# engine_driver.net
KiCad netlist of a schematic drawn in EAGLE
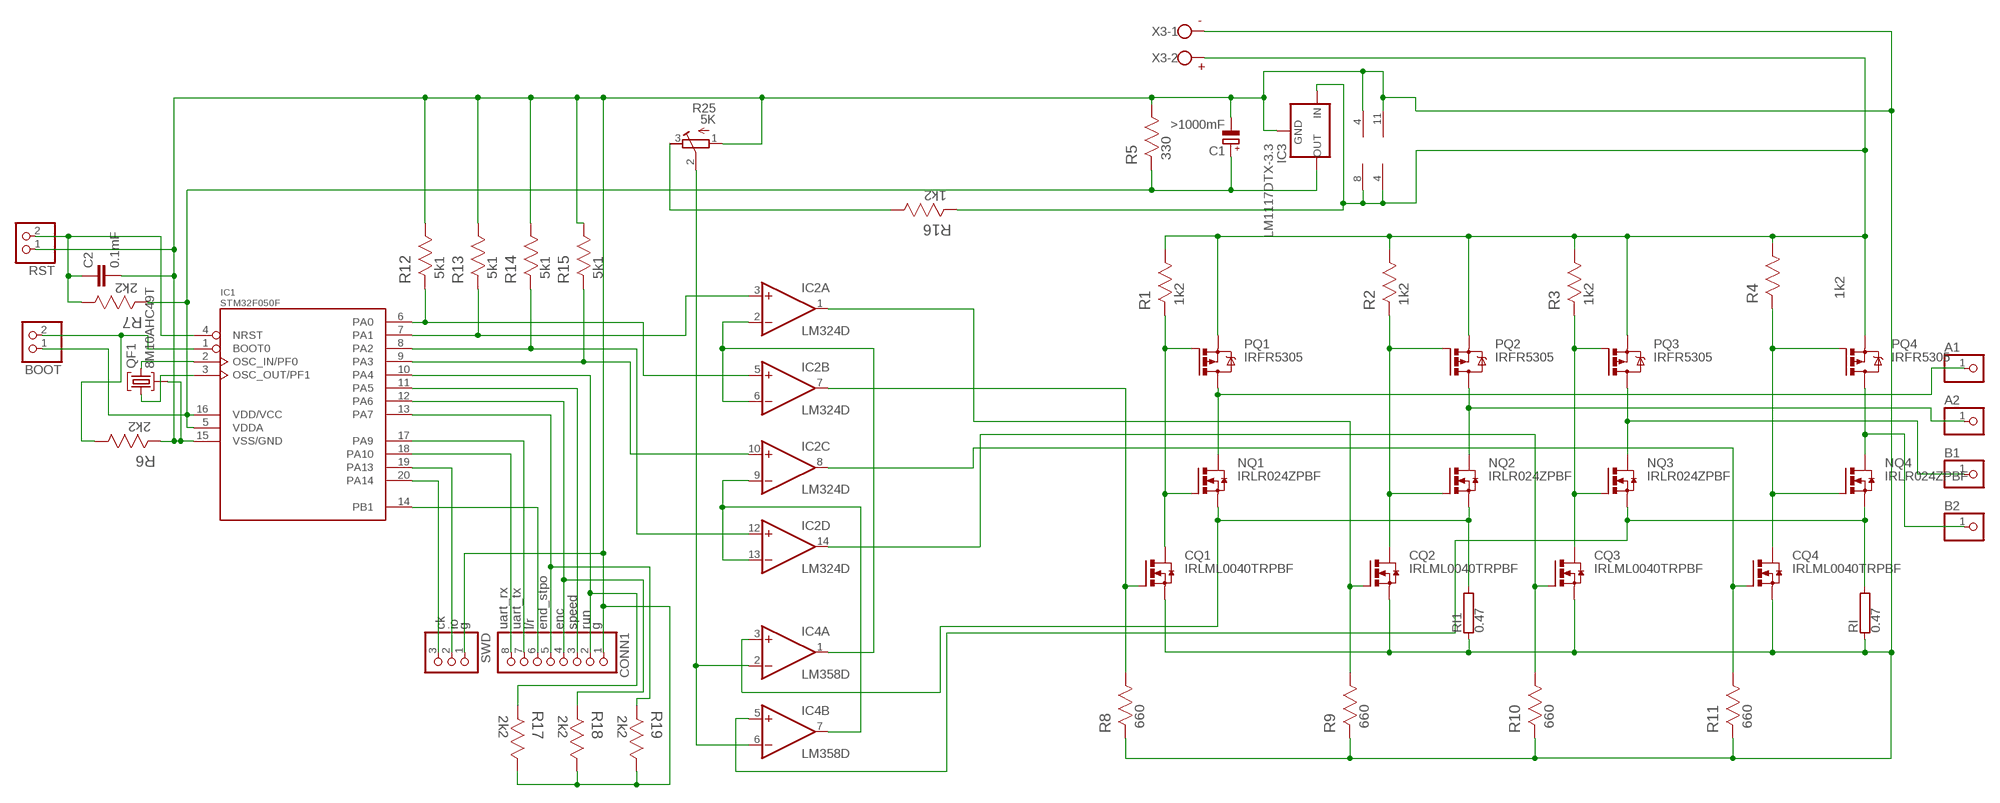
[diagram p0: schematic, sheet 1]

(export (version "E")
  (design (tool "Eeschema 10.0.6"))
  (components
    (comp (ref "A1")
      (value "PINHD-1X1")
      (footprint "eagle-import:1X01")
      (libsource (lib "eagle-import") (part "PINHD-1X1"))
    )
    (comp (ref "A2")
      (value "PINHD-1X1")
      (footprint "eagle-import:1X01")
      (libsource (lib "eagle-import") (part "PINHD-1X1"))
    )
    (comp (ref "B1")
      (value "PINHD-1X1")
      (footprint "eagle-import:1X01")
      (libsource (lib "eagle-import") (part "PINHD-1X1"))
    )
    (comp (ref "B2")
      (value "PINHD-1X1")
      (footprint "eagle-import:1X01")
      (libsource (lib "eagle-import") (part "PINHD-1X1"))
    )
    (comp (ref "BOOT")
      (value "PINHD-1X2")
      (footprint "eagle-import:1X02")
      (libsource (lib "eagle-import") (part "PINHD-1X2"))
    )
    (comp (ref "C1")
      (value ">1000mF")
      (footprint "eagle-import:E2-5")
      (libsource (lib "eagle-import") (part "CPOL-EUE2-5"))
    )
    (comp (ref "C2")
      (value "0.1mF")
      (footprint "eagle-import:C1206")
      (libsource (lib "eagle-import") (part "C-EUC1206"))
    )
    (comp (ref "CONN1")
      (value "PINHD-1X8")
      (footprint "eagle-import:1X08")
      (libsource (lib "eagle-import") (part "PINHD-1X8"))
    )
    (comp (ref "CQ1")
      (value "IRLML0040TRPBF")
      (footprint "eagle-import:MICRO3")
      (libsource (lib "eagle-import") (part "IRLML0040TRPBF"))
    )
    (comp (ref "CQ2")
      (value "IRLML0040TRPBF")
      (footprint "eagle-import:MICRO3")
      (libsource (lib "eagle-import") (part "IRLML0040TRPBF"))
    )
    (comp (ref "CQ3")
      (value "IRLML0040TRPBF")
      (footprint "eagle-import:MICRO3")
      (libsource (lib "eagle-import") (part "IRLML0040TRPBF"))
    )
    (comp (ref "CQ4")
      (value "IRLML0040TRPBF")
      (footprint "eagle-import:MICRO3")
      (libsource (lib "eagle-import") (part "IRLML0040TRPBF"))
    )
    (comp (ref "IC1")
      (value "STM32F050F")
      (footprint "eagle-import:TSSOP20")
      (libsource (lib "eagle-import") (part "STM32F050F"))
    )
    (comp (ref "IC2")
      (value "LM324D")
      (footprint "eagle-import:SO14")
      (libsource (lib "eagle-import") (part "LM324D"))
    )
    (comp (ref "IC3")
      (value "LM1117DTX-3.3")
      (footprint "eagle-import:TO252")
      (libsource (lib "eagle-import") (part "LM1117DTX-3.3"))
    )
    (comp (ref "IC4")
      (value "LM358D")
      (footprint "eagle-import:SO08")
      (libsource (lib "eagle-import") (part "LM358D"))
    )
    (comp (ref "NQ1")
      (value "IRLR024ZPBF")
      (footprint "eagle-import:D-PAK_TO252AA")
      (libsource (lib "eagle-import") (part "IRLR024ZPBF"))
    )
    (comp (ref "NQ2")
      (value "IRLR024ZPBF")
      (footprint "eagle-import:D-PAK_TO252AA")
      (libsource (lib "eagle-import") (part "IRLR024ZPBF"))
    )
    (comp (ref "NQ3")
      (value "IRLR024ZPBF")
      (footprint "eagle-import:D-PAK_TO252AA")
      (libsource (lib "eagle-import") (part "IRLR024ZPBF"))
    )
    (comp (ref "NQ4")
      (value "IRLR024ZPBF")
      (footprint "eagle-import:D-PAK_TO252AA")
      (libsource (lib "eagle-import") (part "IRLR024ZPBF"))
    )
    (comp (ref "PQ1")
      (value "IRFR5305")
      (footprint "eagle-import:D-PAK_TO252AA")
      (libsource (lib "eagle-import") (part "IRF?5305R"))
    )
    (comp (ref "PQ2")
      (value "IRFR5305")
      (footprint "eagle-import:D-PAK_TO252AA")
      (libsource (lib "eagle-import") (part "IRF?5305R"))
    )
    (comp (ref "PQ3")
      (value "IRFR5305")
      (footprint "eagle-import:D-PAK_TO252AA")
      (libsource (lib "eagle-import") (part "IRF?5305R"))
    )
    (comp (ref "PQ4")
      (value "IRFR5305")
      (footprint "eagle-import:D-PAK_TO252AA")
      (libsource (lib "eagle-import") (part "IRF?5305R"))
    )
    (comp (ref "QF1")
      (value "8M10AHC49T")
      (footprint "eagle-import:HC49U")
      (libsource (lib "eagle-import") (part "8M10AHC49T"))
    )
    (comp (ref "R1")
      (value "1k2")
      (footprint "eagle-import:RESC3216X71N")
      (fields (field (name "MPN") "TNPW1206100KBEEA") (field (name "TOLERANCE") "±0.1%"))
      (libsource (lib "eagle-import") (part "TNPW1206100KBEEA"))
    )
    (comp (ref "R2")
      (value "1k2")
      (footprint "eagle-import:RESC3216X71N")
      (fields (field (name "MPN") "TNPW1206100KBEEA") (field (name "TOLERANCE") "±0.1%"))
      (libsource (lib "eagle-import") (part "TNPW1206100KBEEA"))
    )
    (comp (ref "R3")
      (value "1k2")
      (footprint "eagle-import:RESC3216X71N")
      (fields (field (name "MPN") "TNPW1206100KBEEA") (field (name "TOLERANCE") "±0.1%"))
      (libsource (lib "eagle-import") (part "TNPW1206100KBEEA"))
    )
    (comp (ref "R4")
      (value "1k2")
      (footprint "eagle-import:RESC3216X71N")
      (fields (field (name "MPN") "TNPW1206100KBEEA") (field (name "TOLERANCE") "±0.1%"))
      (libsource (lib "eagle-import") (part "TNPW1206100KBEEA"))
    )
    (comp (ref "R5")
      (value "330")
      (footprint "eagle-import:RESC3216X71N")
      (fields (field (name "MPN") "TNPW1206100KBEEA") (field (name "TOLERANCE") "±0.1%"))
      (libsource (lib "eagle-import") (part "TNPW1206100KBEEA"))
    )
    (comp (ref "R6")
      (value "2k2")
      (footprint "eagle-import:RESC3216X71N")
      (fields (field (name "MPN") "TNPW1206100KBEEA") (field (name "TOLERANCE") "±0.1%"))
      (libsource (lib "eagle-import") (part "TNPW1206100KBEEA"))
    )
    (comp (ref "R7")
      (value "2k2")
      (footprint "eagle-import:RESC3216X71N")
      (fields (field (name "MPN") "TNPW1206100KBEEA") (field (name "TOLERANCE") "±0.1%"))
      (libsource (lib "eagle-import") (part "TNPW1206100KBEEA"))
    )
    (comp (ref "R8")
      (value "660")
      (footprint "eagle-import:RESC3216X71N")
      (fields (field (name "MPN") "TNPW1206100KBEEA") (field (name "TOLERANCE") "±0.1%"))
      (libsource (lib "eagle-import") (part "TNPW1206100KBEEA"))
    )
    (comp (ref "R9")
      (value "660")
      (footprint "eagle-import:RESC3216X71N")
      (fields (field (name "MPN") "TNPW1206100KBEEA") (field (name "TOLERANCE") "±0.1%"))
      (libsource (lib "eagle-import") (part "TNPW1206100KBEEA"))
    )
    (comp (ref "R10")
      (value "660")
      (footprint "eagle-import:RESC3216X71N")
      (fields (field (name "MPN") "TNPW1206100KBEEA") (field (name "TOLERANCE") "±0.1%"))
      (libsource (lib "eagle-import") (part "TNPW1206100KBEEA"))
    )
    (comp (ref "R11")
      (value "660")
      (footprint "eagle-import:RESC3216X71N")
      (fields (field (name "MPN") "TNPW1206100KBEEA") (field (name "TOLERANCE") "±0.1%"))
      (libsource (lib "eagle-import") (part "TNPW1206100KBEEA"))
    )
    (comp (ref "R12")
      (value "5k1")
      (footprint "eagle-import:RESC3216X71N")
      (fields (field (name "MPN") "TNPW1206100KBEEA") (field (name "TOLERANCE") "±0.1%"))
      (libsource (lib "eagle-import") (part "TNPW1206100KBEEA"))
    )
    (comp (ref "R13")
      (value "5k1")
      (footprint "eagle-import:RESC3216X71N")
      (fields (field (name "MPN") "TNPW1206100KBEEA") (field (name "TOLERANCE") "±0.1%"))
      (libsource (lib "eagle-import") (part "TNPW1206100KBEEA"))
    )
    (comp (ref "R14")
      (value "5k1")
      (footprint "eagle-import:RESC3216X71N")
      (fields (field (name "MPN") "TNPW1206100KBEEA") (field (name "TOLERANCE") "±0.1%"))
      (libsource (lib "eagle-import") (part "TNPW1206100KBEEA"))
    )
    (comp (ref "R15")
      (value "5k1")
      (footprint "eagle-import:RESC3216X71N")
      (fields (field (name "MPN") "TNPW1206100KBEEA") (field (name "TOLERANCE") "±0.1%"))
      (libsource (lib "eagle-import") (part "TNPW1206100KBEEA"))
    )
    (comp (ref "R16")
      (value "1k2")
      (footprint "eagle-import:RESC3216X71N")
      (fields (field (name "MPN") "TNPW1206100KBEEA") (field (name "TOLERANCE") "±0.1%"))
      (libsource (lib "eagle-import") (part "TNPW1206100KBEEA"))
    )
    (comp (ref "R17")
      (value "2k2")
      (footprint "eagle-import:RESC3216X71N")
      (fields (field (name "MPN") "TNPW1206100KBEEA") (field (name "TOLERANCE") "±0.1%"))
      (libsource (lib "eagle-import") (part "TNPW1206100KBEEA"))
    )
    (comp (ref "R18")
      (value "2k2")
      (footprint "eagle-import:RESC3216X71N")
      (fields (field (name "MPN") "TNPW1206100KBEEA") (field (name "TOLERANCE") "±0.1%"))
      (libsource (lib "eagle-import") (part "TNPW1206100KBEEA"))
    )
    (comp (ref "R19")
      (value "2k2")
      (footprint "eagle-import:RESC3216X71N")
      (fields (field (name "MPN") "TNPW1206100KBEEA") (field (name "TOLERANCE") "±0.1%"))
      (libsource (lib "eagle-import") (part "TNPW1206100KBEEA"))
    )
    (comp (ref "R25")
      (value "5K")
      (footprint "eagle-import:RTRIM5W")
      (libsource (lib "eagle-import") (part "R-TRIMM5W"))
    )
    (comp (ref "RI")
      (value "0.47")
      (footprint "eagle-import:HPS947")
      (libsource (lib "eagle-import") (part "RHPS947"))
    )
    (comp (ref "RI1")
      (value "0.47")
      (footprint "eagle-import:HPS947")
      (libsource (lib "eagle-import") (part "RHPS947"))
    )
    (comp (ref "RST")
      (value "PINHD-1X2")
      (footprint "eagle-import:1X02")
      (libsource (lib "eagle-import") (part "PINHD-1X2"))
    )
    (comp (ref "SWD")
      (value "PINHD-1X3")
      (footprint "eagle-import:1X03")
      (libsource (lib "eagle-import") (part "PINHD-1X3"))
    )
    (comp (ref "X3")
      (value "W237-102")
      (footprint "eagle-import:W237-102")
      (fields (field (name "MPN") "237-102"))
      (libsource (lib "eagle-import") (part "W237-102"))
    )
  )
  (nets
    (net (code "1") (name "Net-(CQ1-D)") (class "Default")
      (node (ref "CQ1") (pin "3") (pinfunction "D_3") (pintype "passive"))
      (node (ref "NQ1") (pin "1") (pinfunction "G_1") (pintype "passive"))
      (node (ref "PQ1") (pin "1") (pinfunction "G_1") (pintype "passive"))
      (node (ref "R1") (pin "2") (pinfunction "2_2") (pintype "passive"))
    )
    (net (code "2") (name "Net-(CQ1-G)") (class "Default")
      (node (ref "CQ1") (pin "1") (pinfunction "G_1") (pintype "passive"))
      (node (ref "IC2") (pin "7") (pinfunction "OUT_7") (pintype "output"))
      (node (ref "R8") (pin "1") (pinfunction "1_1") (pintype "passive"))
    )
    (net (code "3") (name "Net-(CQ1-S)") (class "Default")
      (node (ref "C1") (pin "-") (pinfunction "-_-") (pintype "passive"))
      (node (ref "C2") (pin "2") (pinfunction "2_2") (pintype "passive"))
      (node (ref "CONN1") (pin "1") (pinfunction "1_1") (pintype "passive"))
      (node (ref "CQ1") (pin "2") (pinfunction "S_2") (pintype "passive"))
      (node (ref "CQ2") (pin "2") (pinfunction "S_2") (pintype "passive"))
      (node (ref "CQ3") (pin "2") (pinfunction "S_2") (pintype "passive"))
      (node (ref "CQ4") (pin "2") (pinfunction "S_2") (pintype "passive"))
      (node (ref "IC1") (pin "15") (pinfunction "VSS/GND_15") (pintype "power_in"))
      (node (ref "IC2") (pin "11") (pinfunction "V-_11") (pintype "power_in"))
      (node (ref "IC3") (pin "1") (pinfunction "GND_1") (pintype "input"))
      (node (ref "IC4") (pin "4") (pinfunction "V-_4") (pintype "power_in"))
      (node (ref "QF1") (pin "2") (pinfunction "2_2") (pintype "passive"))
      (node (ref "R10") (pin "2") (pinfunction "2_2") (pintype "passive"))
      (node (ref "R11") (pin "2") (pinfunction "2_2") (pintype "passive"))
      (node (ref "R12") (pin "1") (pinfunction "1_1") (pintype "passive"))
      (node (ref "R13") (pin "1") (pinfunction "1_1") (pintype "passive"))
      (node (ref "R14") (pin "1") (pinfunction "1_1") (pintype "passive"))
      (node (ref "R15") (pin "1") (pinfunction "1_1") (pintype "passive"))
      (node (ref "R17") (pin "1") (pinfunction "1_1") (pintype "passive"))
      (node (ref "R18") (pin "1") (pinfunction "1_1") (pintype "passive"))
      (node (ref "R19") (pin "1") (pinfunction "1_1") (pintype "passive"))
      (node (ref "R25") (pin "1") (pinfunction "A_1") (pintype "passive"))
      (node (ref "R5") (pin "1") (pinfunction "1_1") (pintype "passive"))
      (node (ref "R6") (pin "2") (pinfunction "2_2") (pintype "passive"))
      (node (ref "R8") (pin "2") (pinfunction "2_2") (pintype "passive"))
      (node (ref "R9") (pin "2") (pinfunction "2_2") (pintype "passive"))
      (node (ref "RI") (pin "1") (pinfunction "1_1") (pintype "passive"))
      (node (ref "RI1") (pin "1") (pinfunction "1_1") (pintype "passive"))
      (node (ref "RST") (pin "1") (pinfunction "1_1") (pintype "passive"))
      (node (ref "SWD") (pin "1") (pinfunction "1_1") (pintype "passive"))
      (node (ref "X3") (pin "1") (pinfunction "KL_1") (pintype "passive"))
    )
    (net (code "4") (name "Net-(CQ2-D)") (class "Default")
      (node (ref "CQ2") (pin "3") (pinfunction "D_3") (pintype "passive"))
      (node (ref "NQ2") (pin "1") (pinfunction "G_1") (pintype "passive"))
      (node (ref "PQ2") (pin "1") (pinfunction "G_1") (pintype "passive"))
      (node (ref "R2") (pin "2") (pinfunction "2_2") (pintype "passive"))
    )
    (net (code "5") (name "Net-(CQ2-G)") (class "Default")
      (node (ref "CQ2") (pin "1") (pinfunction "G_1") (pintype "passive"))
      (node (ref "IC2") (pin "1") (pinfunction "OUT_1") (pintype "output"))
      (node (ref "R9") (pin "1") (pinfunction "1_1") (pintype "passive"))
    )
    (net (code "6") (name "Net-(CQ3-D)") (class "Default")
      (node (ref "CQ3") (pin "3") (pinfunction "D_3") (pintype "passive"))
      (node (ref "NQ3") (pin "1") (pinfunction "G_1") (pintype "passive"))
      (node (ref "PQ3") (pin "1") (pinfunction "G_1") (pintype "passive"))
      (node (ref "R3") (pin "2") (pinfunction "2_2") (pintype "passive"))
    )
    (net (code "7") (name "Net-(CQ3-G)") (class "Default")
      (node (ref "CQ3") (pin "1") (pinfunction "G_1") (pintype "passive"))
      (node (ref "IC2") (pin "14") (pinfunction "OUT_14") (pintype "output"))
      (node (ref "R10") (pin "1") (pinfunction "1_1") (pintype "passive"))
    )
    (net (code "8") (name "Net-(CQ4-D)") (class "Default")
      (node (ref "CQ4") (pin "3") (pinfunction "D_3") (pintype "passive"))
      (node (ref "NQ4") (pin "1") (pinfunction "G_1") (pintype "passive"))
      (node (ref "PQ4") (pin "1") (pinfunction "G_1") (pintype "passive"))
      (node (ref "R4") (pin "2") (pinfunction "2_2") (pintype "passive"))
    )
    (net (code "9") (name "Net-(CQ4-G)") (class "Default")
      (node (ref "CQ4") (pin "1") (pinfunction "G_1") (pintype "passive"))
      (node (ref "IC2") (pin "8") (pinfunction "OUT_8") (pintype "output"))
      (node (ref "R11") (pin "1") (pinfunction "1_1") (pintype "passive"))
    )
    (net (code "10") (name "Net-(IC1-BOOT0)") (class "Default")
      (node (ref "BOOT") (pin "2") (pinfunction "2_2") (pintype "passive"))
      (node (ref "IC1") (pin "1") (pinfunction "BOOT0_1") (pintype "bidirectional"))
      (node (ref "R6") (pin "1") (pinfunction "1_1") (pintype "passive"))
    )
    (net (code "11") (name "Net-(IC1-NRST)") (class "Default")
      (node (ref "C2") (pin "1") (pinfunction "1_1") (pintype "passive"))
      (node (ref "IC1") (pin "4") (pinfunction "NRST_4") (pintype "bidirectional"))
      (node (ref "R7") (pin "1") (pinfunction "1_1") (pintype "passive"))
      (node (ref "RST") (pin "2") (pinfunction "2_2") (pintype "passive"))
    )
    (net (code "12") (name "Net-(IC1-OSC_IN{slash}PF0)") (class "Default")
      (node (ref "IC1") (pin "2") (pinfunction "OSC_IN/PF0_2") (pintype "bidirectional"))
      (node (ref "QF1") (pin "3") (pinfunction "3_3") (pintype "passive"))
    )
    (net (code "13") (name "Net-(IC1-OSC_OUT{slash}PF1)") (class "Default")
      (node (ref "IC1") (pin "3") (pinfunction "OSC_OUT/PF1_3") (pintype "bidirectional"))
      (node (ref "QF1") (pin "1") (pinfunction "1_1") (pintype "passive"))
    )
    (net (code "14") (name "Net-(IC1-PA0)") (class "Default")
      (node (ref "IC1") (pin "6") (pinfunction "PA0_6") (pintype "bidirectional"))
      (node (ref "IC2") (pin "5") (pinfunction "+IN_5") (pintype "input"))
      (node (ref "R12") (pin "2") (pinfunction "2_2") (pintype "passive"))
    )
    (net (code "15") (name "Net-(IC1-PA1)") (class "Default")
      (node (ref "IC1") (pin "7") (pinfunction "PA1_7") (pintype "bidirectional"))
      (node (ref "IC2") (pin "3") (pinfunction "+IN_3") (pintype "input"))
      (node (ref "R13") (pin "2") (pinfunction "2_2") (pintype "passive"))
    )
    (net (code "16") (name "Net-(IC1-PA2)") (class "Default")
      (node (ref "IC1") (pin "8") (pinfunction "PA2_8") (pintype "bidirectional"))
      (node (ref "IC2") (pin "12") (pinfunction "+IN_12") (pintype "input"))
      (node (ref "R14") (pin "2") (pinfunction "2_2") (pintype "passive"))
    )
    (net (code "17") (name "Net-(IC1-PA3)") (class "Default")
      (node (ref "IC1") (pin "9") (pinfunction "PA3_9") (pintype "bidirectional"))
      (node (ref "IC2") (pin "10") (pinfunction "+IN_10") (pintype "input"))
      (node (ref "R15") (pin "2") (pinfunction "2_2") (pintype "passive"))
    )
    (net (code "18") (name "Net-(IC1-PA4)") (class "Default")
      (node (ref "CONN1") (pin "2") (pinfunction "2_2") (pintype "passive"))
      (node (ref "IC1") (pin "10") (pinfunction "PA4_10") (pintype "bidirectional"))
      (node (ref "R17") (pin "2") (pinfunction "2_2") (pintype "passive"))
    )
    (net (code "19") (name "Net-(IC1-PA5)") (class "Default")
      (node (ref "CONN1") (pin "3") (pinfunction "3_3") (pintype "passive"))
      (node (ref "IC1") (pin "11") (pinfunction "PA5_11") (pintype "bidirectional"))
    )
    (net (code "20") (name "Net-(IC1-PA6)") (class "Default")
      (node (ref "CONN1") (pin "4") (pinfunction "4_4") (pintype "passive"))
      (node (ref "IC1") (pin "12") (pinfunction "PA6_12") (pintype "bidirectional"))
      (node (ref "R18") (pin "2") (pinfunction "2_2") (pintype "passive"))
    )
    (net (code "21") (name "Net-(IC1-PA7)") (class "Default")
      (node (ref "CONN1") (pin "5") (pinfunction "5_5") (pintype "passive"))
      (node (ref "IC1") (pin "13") (pinfunction "PA7_13") (pintype "bidirectional"))
      (node (ref "R19") (pin "2") (pinfunction "2_2") (pintype "passive"))
    )
    (net (code "22") (name "Net-(IC1-PA9)") (class "Default")
      (node (ref "CONN1") (pin "7") (pinfunction "7_7") (pintype "passive"))
      (node (ref "IC1") (pin "17") (pinfunction "PA9_17") (pintype "bidirectional"))
    )
    (net (code "23") (name "Net-(IC1-PA10)") (class "Default")
      (node (ref "CONN1") (pin "8") (pinfunction "8_8") (pintype "passive"))
      (node (ref "IC1") (pin "18") (pinfunction "PA10_18") (pintype "bidirectional"))
    )
    (net (code "24") (name "Net-(IC1-PA13)") (class "Default")
      (node (ref "IC1") (pin "19") (pinfunction "PA13_19") (pintype "bidirectional"))
      (node (ref "SWD") (pin "2") (pinfunction "2_2") (pintype "passive"))
    )
    (net (code "25") (name "Net-(IC1-PA14)") (class "Default")
      (node (ref "IC1") (pin "20") (pinfunction "PA14_20") (pintype "bidirectional"))
      (node (ref "SWD") (pin "3") (pinfunction "3_3") (pintype "passive"))
    )
    (net (code "26") (name "Net-(IC1-PB1)") (class "Default")
      (node (ref "CONN1") (pin "6") (pinfunction "6_6") (pintype "passive"))
      (node (ref "IC1") (pin "14") (pinfunction "PB1_14") (pintype "bidirectional"))
    )
    (net (code "27") (name "Net-(IC1-VDDA)") (class "Default")
      (node (ref "BOOT") (pin "1") (pinfunction "1_1") (pintype "passive"))
      (node (ref "C1") (pin "+") (pinfunction "+_+") (pintype "passive"))
      (node (ref "IC1") (pin "16") (pinfunction "VDD/VCC_16") (pintype "power_in"))
      (node (ref "IC1") (pin "5") (pinfunction "VDDA_5") (pintype "power_in"))
      (node (ref "IC3") (pin "TAB") (pinfunction "OUT_TAB") (pintype "passive"))
      (node (ref "R5") (pin "2") (pinfunction "2_2") (pintype "passive"))
      (node (ref "R7") (pin "2") (pinfunction "2_2") (pintype "passive"))
    )
    (net (code "28") (name "Net-(IC2A--IN)") (class "Default")
      (node (ref "IC2") (pin "2") (pinfunction "-IN_2") (pintype "input"))
      (node (ref "IC2") (pin "6") (pinfunction "-IN_6") (pintype "input"))
      (node (ref "IC4") (pin "1") (pinfunction "OUT_1") (pintype "output"))
    )
    (net (code "29") (name "Net-(IC2C--IN)") (class "Default")
      (node (ref "IC2") (pin "13") (pinfunction "-IN_13") (pintype "input"))
      (node (ref "IC2") (pin "9") (pinfunction "-IN_9") (pintype "input"))
      (node (ref "IC4") (pin "7") (pinfunction "OUT_7") (pintype "output"))
    )
    (net (code "30") (name "Net-(IC2E-V+)") (class "Default")
      (node (ref "IC2") (pin "4") (pinfunction "V+_4") (pintype "power_in"))
      (node (ref "IC3") (pin "2") (pinfunction "IN_2") (pintype "input"))
      (node (ref "IC4") (pin "8") (pinfunction "V+_8") (pintype "power_in"))
      (node (ref "PQ1") (pin "3") (pinfunction "S_3") (pintype "passive"))
      (node (ref "PQ2") (pin "3") (pinfunction "S_3") (pintype "passive"))
      (node (ref "PQ3") (pin "3") (pinfunction "S_3") (pintype "passive"))
      (node (ref "PQ4") (pin "3") (pinfunction "S_3") (pintype "passive"))
      (node (ref "R1") (pin "1") (pinfunction "1_1") (pintype "passive"))
      (node (ref "R16") (pin "2") (pinfunction "2_2") (pintype "passive"))
      (node (ref "R2") (pin "1") (pinfunction "1_1") (pintype "passive"))
      (node (ref "R3") (pin "1") (pinfunction "1_1") (pintype "passive"))
      (node (ref "R4") (pin "1") (pinfunction "1_1") (pintype "passive"))
      (node (ref "X3") (pin "2") (pinfunction "KL_2") (pintype "passive"))
    )
    (net (code "31") (name "Net-(IC4A-+IN)") (class "Default")
      (node (ref "IC4") (pin "3") (pinfunction "+IN_3") (pintype "input"))
      (node (ref "NQ1") (pin "3") (pinfunction "S_3") (pintype "passive"))
      (node (ref "NQ2") (pin "3") (pinfunction "S_3") (pintype "passive"))
      (node (ref "RI1") (pin "2") (pinfunction "2_2") (pintype "passive"))
    )
    (net (code "32") (name "Net-(IC4A--IN)") (class "Default")
      (node (ref "IC4") (pin "2") (pinfunction "-IN_2") (pintype "input"))
      (node (ref "IC4") (pin "6") (pinfunction "-IN_6") (pintype "input"))
      (node (ref "R25") (pin "2") (pinfunction "S_2") (pintype "passive"))
    )
    (net (code "33") (name "Net-(IC4B-+IN)") (class "Default")
      (node (ref "IC4") (pin "5") (pinfunction "+IN_5") (pintype "input"))
      (node (ref "NQ3") (pin "3") (pinfunction "S_3") (pintype "passive"))
      (node (ref "NQ4") (pin "3") (pinfunction "S_3") (pintype "passive"))
      (node (ref "RI") (pin "2") (pinfunction "2_2") (pintype "passive"))
    )
    (net (code "34") (name "Net-(NQ1-D)") (class "Default")
      (node (ref "A1") (pin "1") (pinfunction "1_1") (pintype "passive"))
      (node (ref "NQ1") (pin "4") (pinfunction "D_4") (pintype "passive"))
      (node (ref "PQ1") (pin "4") (pinfunction "D_4") (pintype "passive"))
    )
    (net (code "35") (name "Net-(NQ2-D)") (class "Default")
      (node (ref "A2") (pin "1") (pinfunction "1_1") (pintype "passive"))
      (node (ref "NQ2") (pin "4") (pinfunction "D_4") (pintype "passive"))
      (node (ref "PQ2") (pin "4") (pinfunction "D_4") (pintype "passive"))
    )
    (net (code "36") (name "Net-(NQ3-D)") (class "Default")
      (node (ref "B1") (pin "1") (pinfunction "1_1") (pintype "passive"))
      (node (ref "NQ3") (pin "4") (pinfunction "D_4") (pintype "passive"))
      (node (ref "PQ3") (pin "4") (pinfunction "D_4") (pintype "passive"))
    )
    (net (code "37") (name "Net-(NQ4-D)") (class "Default")
      (node (ref "B2") (pin "1") (pinfunction "1_1") (pintype "passive"))
      (node (ref "NQ4") (pin "4") (pinfunction "D_4") (pintype "passive"))
      (node (ref "PQ4") (pin "4") (pinfunction "D_4") (pintype "passive"))
    )
    (net (code "38") (name "Net-(R25-E)") (class "Default")
      (node (ref "R16") (pin "1") (pinfunction "1_1") (pintype "passive"))
      (node (ref "R25") (pin "3") (pinfunction "E_3") (pintype "passive"))
    )
  )
)
